# ExternalConnection.net
KiCad netlist of a schematic drawn in Altium Designer
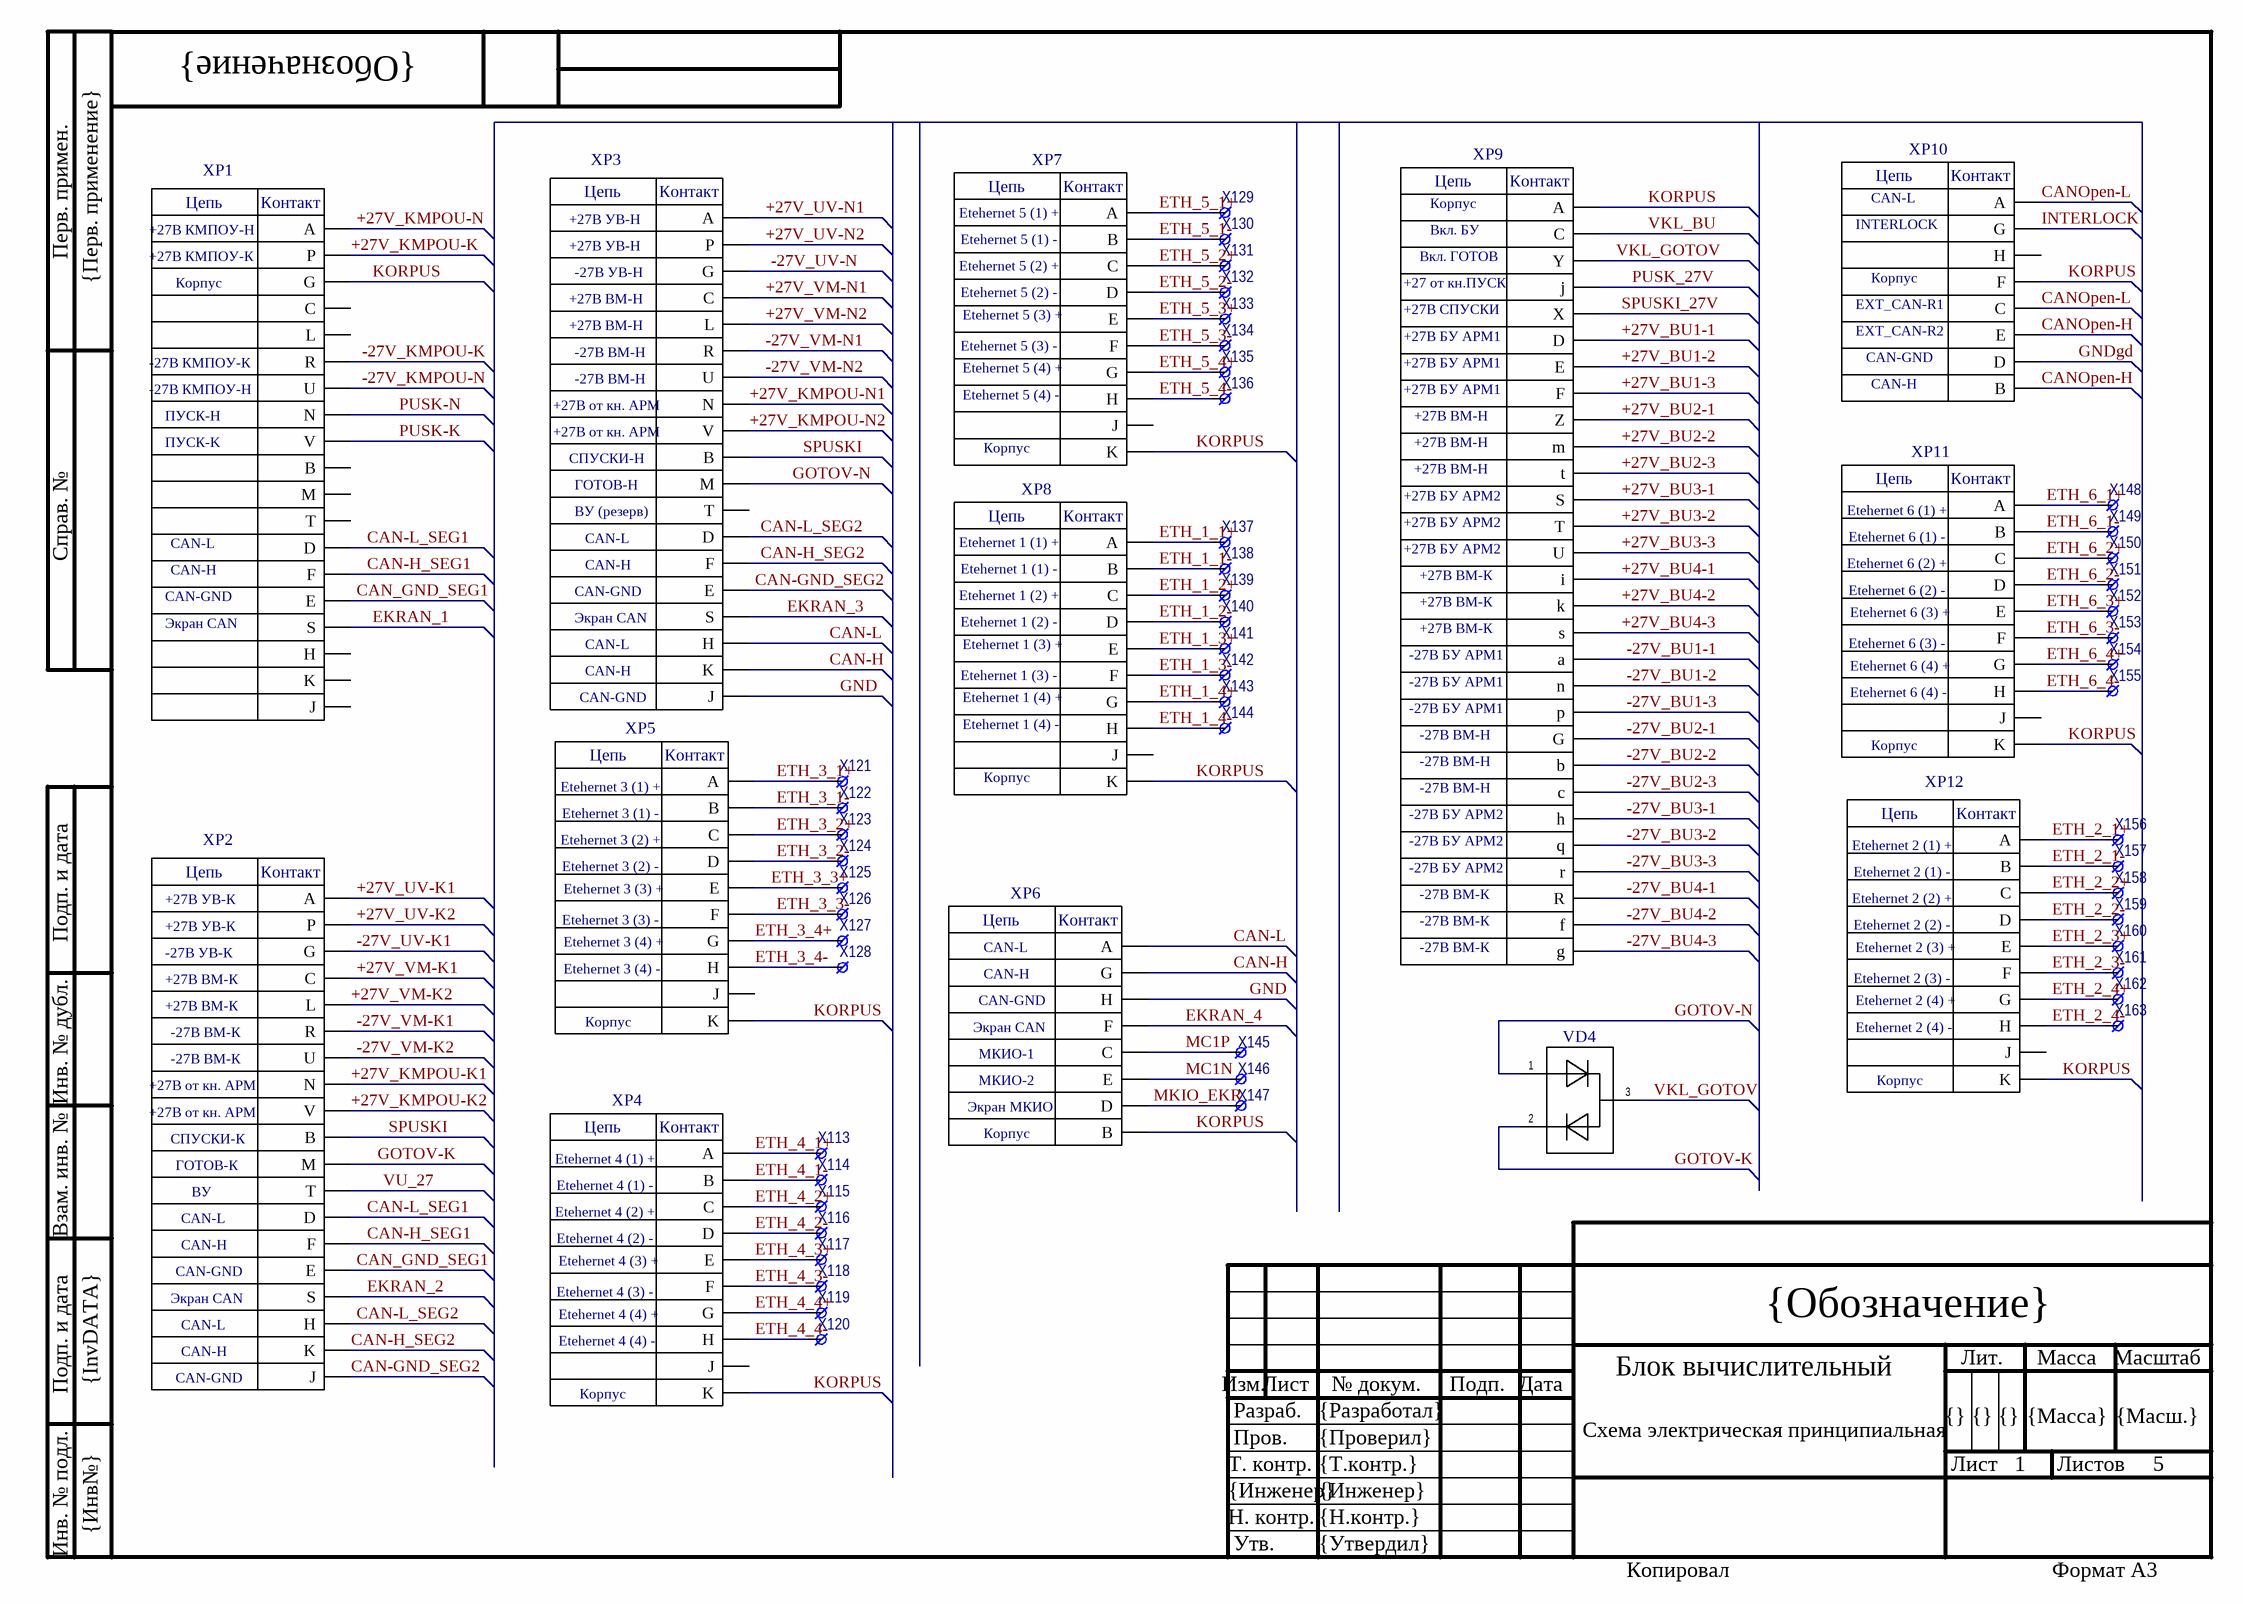
[diagram p0: ExternalConnection.SchDoc]

(export (version "E")
  (design (tool "Eeschema 10.0.6"))
  (components
    (comp (ref "VD4")
      (value "2Д707АС9")
      (footprint "KT-46")
      (description "2Д707АС9 диод импульсный")
      (libsource (lib "Блок вычислительный") (part "2Д707АС9"))
    )
    (comp (ref "X113")
      (value "CONT")
      (footprint "ПЛАН_ПЛОЩ")
      (description "CONT1_SMD")
      (fields (field (name "PARTNUMBER") "контактное поле"))
      (libsource (lib "Блок вычислительный") (part "CONT"))
    )
    (comp (ref "X114")
      (value "CONT")
      (footprint "ПЛАН_ПЛОЩ")
      (description "CONT1_SMD")
      (fields (field (name "PARTNUMBER") "контактное поле"))
      (libsource (lib "Блок вычислительный") (part "CONT"))
    )
    (comp (ref "X115")
      (value "CONT")
      (footprint "ПЛАН_ПЛОЩ")
      (description "CONT1_SMD")
      (fields (field (name "PARTNUMBER") "контактное поле"))
      (libsource (lib "Блок вычислительный") (part "CONT"))
    )
    (comp (ref "X116")
      (value "CONT")
      (footprint "ПЛАН_ПЛОЩ")
      (description "CONT1_SMD")
      (fields (field (name "PARTNUMBER") "контактное поле"))
      (libsource (lib "Блок вычислительный") (part "CONT"))
    )
    (comp (ref "X117")
      (value "CONT")
      (footprint "ПЛАН_ПЛОЩ")
      (description "CONT1_SMD")
      (fields (field (name "PARTNUMBER") "контактное поле"))
      (libsource (lib "Блок вычислительный") (part "CONT"))
    )
    (comp (ref "X118")
      (value "CONT")
      (footprint "ПЛАН_ПЛОЩ")
      (description "CONT1_SMD")
      (fields (field (name "PARTNUMBER") "контактное поле"))
      (libsource (lib "Блок вычислительный") (part "CONT"))
    )
    (comp (ref "X119")
      (value "CONT")
      (footprint "ПЛАН_ПЛОЩ")
      (description "CONT1_SMD")
      (fields (field (name "PARTNUMBER") "контактное поле"))
      (libsource (lib "Блок вычислительный") (part "CONT"))
    )
    (comp (ref "X120")
      (value "CONT")
      (footprint "ПЛАН_ПЛОЩ")
      (description "CONT1_SMD")
      (fields (field (name "PARTNUMBER") "контактное поле"))
      (libsource (lib "Блок вычислительный") (part "CONT"))
    )
    (comp (ref "X121")
      (value "CONT")
      (footprint "ПЛАН_ПЛОЩ")
      (description "CONT1_SMD")
      (fields (field (name "PARTNUMBER") "контактное поле"))
      (libsource (lib "Блок вычислительный") (part "CONT"))
    )
    (comp (ref "X122")
      (value "CONT")
      (footprint "ПЛАН_ПЛОЩ")
      (description "CONT1_SMD")
      (fields (field (name "PARTNUMBER") "контактное поле"))
      (libsource (lib "Блок вычислительный") (part "CONT"))
    )
    (comp (ref "X123")
      (value "CONT")
      (footprint "ПЛАН_ПЛОЩ")
      (description "CONT1_SMD")
      (fields (field (name "PARTNUMBER") "контактное поле"))
      (libsource (lib "Блок вычислительный") (part "CONT"))
    )
    (comp (ref "X124")
      (value "CONT")
      (footprint "ПЛАН_ПЛОЩ")
      (description "CONT1_SMD")
      (fields (field (name "PARTNUMBER") "контактное поле"))
      (libsource (lib "Блок вычислительный") (part "CONT"))
    )
    (comp (ref "X125")
      (value "CONT")
      (footprint "ПЛАН_ПЛОЩ")
      (description "CONT1_SMD")
      (fields (field (name "PARTNUMBER") "контактное поле"))
      (libsource (lib "Блок вычислительный") (part "CONT"))
    )
    (comp (ref "X126")
      (value "CONT")
      (footprint "ПЛАН_ПЛОЩ")
      (description "CONT1_SMD")
      (fields (field (name "PARTNUMBER") "контактное поле"))
      (libsource (lib "Блок вычислительный") (part "CONT"))
    )
    (comp (ref "X127")
      (value "CONT")
      (footprint "ПЛАН_ПЛОЩ")
      (description "CONT1_SMD")
      (fields (field (name "PARTNUMBER") "контактное поле"))
      (libsource (lib "Блок вычислительный") (part "CONT"))
    )
    (comp (ref "X128")
      (value "CONT")
      (footprint "ПЛАН_ПЛОЩ")
      (description "CONT1_SMD")
      (fields (field (name "PARTNUMBER") "контактное поле"))
      (libsource (lib "Блок вычислительный") (part "CONT"))
    )
    (comp (ref "X129")
      (value "CONT")
      (footprint "ПЛАН_ПЛОЩ")
      (description "CONT1_SMD")
      (fields (field (name "PARTNUMBER") "контактное поле"))
      (libsource (lib "Блок вычислительный") (part "CONT"))
    )
    (comp (ref "X130")
      (value "CONT")
      (footprint "ПЛАН_ПЛОЩ")
      (description "CONT1_SMD")
      (fields (field (name "PARTNUMBER") "контактное поле"))
      (libsource (lib "Блок вычислительный") (part "CONT"))
    )
    (comp (ref "X131")
      (value "CONT")
      (footprint "ПЛАН_ПЛОЩ")
      (description "CONT1_SMD")
      (fields (field (name "PARTNUMBER") "контактное поле"))
      (libsource (lib "Блок вычислительный") (part "CONT"))
    )
    (comp (ref "X132")
      (value "CONT")
      (footprint "ПЛАН_ПЛОЩ")
      (description "CONT1_SMD")
      (fields (field (name "PARTNUMBER") "контактное поле"))
      (libsource (lib "Блок вычислительный") (part "CONT"))
    )
    (comp (ref "X133")
      (value "CONT")
      (footprint "ПЛАН_ПЛОЩ")
      (description "CONT1_SMD")
      (fields (field (name "PARTNUMBER") "контактное поле"))
      (libsource (lib "Блок вычислительный") (part "CONT"))
    )
    (comp (ref "X134")
      (value "CONT")
      (footprint "ПЛАН_ПЛОЩ")
      (description "CONT1_SMD")
      (fields (field (name "PARTNUMBER") "контактное поле"))
      (libsource (lib "Блок вычислительный") (part "CONT"))
    )
    (comp (ref "X135")
      (value "CONT")
      (footprint "ПЛАН_ПЛОЩ")
      (description "CONT1_SMD")
      (fields (field (name "PARTNUMBER") "контактное поле"))
      (libsource (lib "Блок вычислительный") (part "CONT"))
    )
    (comp (ref "X136")
      (value "CONT")
      (footprint "ПЛАН_ПЛОЩ")
      (description "CONT1_SMD")
      (fields (field (name "PARTNUMBER") "контактное поле"))
      (libsource (lib "Блок вычислительный") (part "CONT"))
    )
    (comp (ref "X137")
      (value "CONT")
      (footprint "ПЛАН_ПЛОЩ")
      (description "CONT1_SMD")
      (fields (field (name "PARTNUMBER") "контактное поле"))
      (libsource (lib "Блок вычислительный") (part "CONT"))
    )
    (comp (ref "X138")
      (value "CONT")
      (footprint "ПЛАН_ПЛОЩ")
      (description "CONT1_SMD")
      (fields (field (name "PARTNUMBER") "контактное поле"))
      (libsource (lib "Блок вычислительный") (part "CONT"))
    )
    (comp (ref "X139")
      (value "CONT")
      (footprint "ПЛАН_ПЛОЩ")
      (description "CONT1_SMD")
      (fields (field (name "PARTNUMBER") "контактное поле"))
      (libsource (lib "Блок вычислительный") (part "CONT"))
    )
    (comp (ref "X140")
      (value "CONT")
      (footprint "ПЛАН_ПЛОЩ")
      (description "CONT1_SMD")
      (fields (field (name "PARTNUMBER") "контактное поле"))
      (libsource (lib "Блок вычислительный") (part "CONT"))
    )
    (comp (ref "X141")
      (value "CONT")
      (footprint "ПЛАН_ПЛОЩ")
      (description "CONT1_SMD")
      (fields (field (name "PARTNUMBER") "контактное поле"))
      (libsource (lib "Блок вычислительный") (part "CONT"))
    )
    (comp (ref "X142")
      (value "CONT")
      (footprint "ПЛАН_ПЛОЩ")
      (description "CONT1_SMD")
      (fields (field (name "PARTNUMBER") "контактное поле"))
      (libsource (lib "Блок вычислительный") (part "CONT"))
    )
    (comp (ref "X143")
      (value "CONT")
      (footprint "ПЛАН_ПЛОЩ")
      (description "CONT1_SMD")
      (fields (field (name "PARTNUMBER") "контактное поле"))
      (libsource (lib "Блок вычислительный") (part "CONT"))
    )
    (comp (ref "X144")
      (value "CONT")
      (footprint "ПЛАН_ПЛОЩ")
      (description "CONT1_SMD")
      (fields (field (name "PARTNUMBER") "контактное поле"))
      (libsource (lib "Блок вычислительный") (part "CONT"))
    )
    (comp (ref "X145")
      (value "CONT")
      (footprint "ПЛАН_ПЛОЩ")
      (description "CONT1_SMD")
      (fields (field (name "PARTNUMBER") "контактное поле"))
      (libsource (lib "Блок вычислительный") (part "CONT"))
    )
    (comp (ref "X146")
      (value "CONT")
      (footprint "ПЛАН_ПЛОЩ")
      (description "CONT1_SMD")
      (fields (field (name "PARTNUMBER") "контактное поле"))
      (libsource (lib "Блок вычислительный") (part "CONT"))
    )
    (comp (ref "X147")
      (value "CONT")
      (footprint "ПЛАН_ПЛОЩ")
      (description "CONT1_SMD")
      (fields (field (name "PARTNUMBER") "контактное поле"))
      (libsource (lib "Блок вычислительный") (part "CONT"))
    )
    (comp (ref "X148")
      (value "CONT")
      (footprint "ПЛАН_ПЛОЩ")
      (description "CONT1_SMD")
      (fields (field (name "PARTNUMBER") "контактное поле"))
      (libsource (lib "Блок вычислительный") (part "CONT"))
    )
    (comp (ref "X149")
      (value "CONT")
      (footprint "ПЛАН_ПЛОЩ")
      (description "CONT1_SMD")
      (fields (field (name "PARTNUMBER") "контактное поле"))
      (libsource (lib "Блок вычислительный") (part "CONT"))
    )
    (comp (ref "X150")
      (value "CONT")
      (footprint "ПЛАН_ПЛОЩ")
      (description "CONT1_SMD")
      (fields (field (name "PARTNUMBER") "контактное поле"))
      (libsource (lib "Блок вычислительный") (part "CONT"))
    )
    (comp (ref "X151")
      (value "CONT")
      (footprint "ПЛАН_ПЛОЩ")
      (description "CONT1_SMD")
      (fields (field (name "PARTNUMBER") "контактное поле"))
      (libsource (lib "Блок вычислительный") (part "CONT"))
    )
    (comp (ref "X152")
      (value "CONT")
      (footprint "ПЛАН_ПЛОЩ")
      (description "CONT1_SMD")
      (fields (field (name "PARTNUMBER") "контактное поле"))
      (libsource (lib "Блок вычислительный") (part "CONT"))
    )
    (comp (ref "X153")
      (value "CONT")
      (footprint "ПЛАН_ПЛОЩ")
      (description "CONT1_SMD")
      (fields (field (name "PARTNUMBER") "контактное поле"))
      (libsource (lib "Блок вычислительный") (part "CONT"))
    )
    (comp (ref "X154")
      (value "CONT")
      (footprint "ПЛАН_ПЛОЩ")
      (description "CONT1_SMD")
      (fields (field (name "PARTNUMBER") "контактное поле"))
      (libsource (lib "Блок вычислительный") (part "CONT"))
    )
    (comp (ref "X155")
      (value "CONT")
      (footprint "ПЛАН_ПЛОЩ")
      (description "CONT1_SMD")
      (fields (field (name "PARTNUMBER") "контактное поле"))
      (libsource (lib "Блок вычислительный") (part "CONT"))
    )
    (comp (ref "X156")
      (value "CONT")
      (footprint "ПЛАН_ПЛОЩ")
      (description "CONT1_SMD")
      (fields (field (name "PARTNUMBER") "контактное поле"))
      (libsource (lib "Блок вычислительный") (part "CONT"))
    )
    (comp (ref "X157")
      (value "CONT")
      (footprint "ПЛАН_ПЛОЩ")
      (description "CONT1_SMD")
      (fields (field (name "PARTNUMBER") "контактное поле"))
      (libsource (lib "Блок вычислительный") (part "CONT"))
    )
    (comp (ref "X158")
      (value "CONT")
      (footprint "ПЛАН_ПЛОЩ")
      (description "CONT1_SMD")
      (fields (field (name "PARTNUMBER") "контактное поле"))
      (libsource (lib "Блок вычислительный") (part "CONT"))
    )
    (comp (ref "X159")
      (value "CONT")
      (footprint "ПЛАН_ПЛОЩ")
      (description "CONT1_SMD")
      (fields (field (name "PARTNUMBER") "контактное поле"))
      (libsource (lib "Блок вычислительный") (part "CONT"))
    )
    (comp (ref "X160")
      (value "CONT")
      (footprint "ПЛАН_ПЛОЩ")
      (description "CONT1_SMD")
      (fields (field (name "PARTNUMBER") "контактное поле"))
      (libsource (lib "Блок вычислительный") (part "CONT"))
    )
    (comp (ref "X161")
      (value "CONT")
      (footprint "ПЛАН_ПЛОЩ")
      (description "CONT1_SMD")
      (fields (field (name "PARTNUMBER") "контактное поле"))
      (libsource (lib "Блок вычислительный") (part "CONT"))
    )
    (comp (ref "X162")
      (value "CONT")
      (footprint "ПЛАН_ПЛОЩ")
      (description "CONT1_SMD")
      (fields (field (name "PARTNUMBER") "контактное поле"))
      (libsource (lib "Блок вычислительный") (part "CONT"))
    )
    (comp (ref "X163")
      (value "CONT")
      (footprint "ПЛАН_ПЛОЩ")
      (description "CONT1_SMD")
      (fields (field (name "PARTNUMBER") "контактное поле"))
      (libsource (lib "Блок вычислительный") (part "CONT"))
    )
    (comp (ref "XP1")
      (value "СНЦ144-19")
      (footprint "блок вычислительный_v1:XP_СНЦ144-19/15-вилка")
      (description "ВИЛКА СНЦ144-19 СОСТАВНАЯ")
      (fields (field (name "PARTNUMBER") "СНЦ144-19/15ВП21-NWПС"))
      (libsource (lib "Блок вычислительный") (part "СНЦ144-19"))
    )
    (comp (ref "XP2")
      (value "СНЦ144-19")
      (footprint "блок вычислительный_v1:XP_СНЦ144-19/15-вилка")
      (description "ВИЛКА СНЦ144-19 СОСТАВНАЯ")
      (fields (field (name "PARTNUMBER") "СНЦ144-19/15ВП21-NWПС"))
      (libsource (lib "Блок вычислительный") (part "СНЦ144-19"))
    )
    (comp (ref "XP3")
      (value "СНЦ144-19")
      (footprint "блок вычислительный_v1:XP_СНЦ144-19/15-вилка")
      (description "ВИЛКА СНЦ144-19 СОСТАВНАЯ")
      (fields (field (name "PARTNUMBER") "СНЦ144-19/15ВП21-NWПС"))
      (libsource (lib "Блок вычислительный") (part "СНЦ144-19"))
    )
    (comp (ref "XP4")
      (value "СНЦ144-10")
      (footprint "блок вычислительный_v1:XP_СНЦ144-10_13-вилка")
      (description "ВИЛКА СНЦ144-10 СОСТАВНАЯ")
      (fields (field (name "PARTNUMBER") "СНЦ144-10/13ВП21-NWПС"))
      (libsource (lib "Блок вычислительный") (part "СНЦ144-10"))
    )
    (comp (ref "XP5")
      (value "СНЦ144-10")
      (footprint "блок вычислительный_v1:XP_СНЦ144-10_13-вилка")
      (description "ВИЛКА СНЦ144-10 СОСТАВНАЯ")
      (fields (field (name "PARTNUMBER") "СНЦ144-10/13ВП21-NWПС"))
      (libsource (lib "Блок вычислительный") (part "СНЦ144-10"))
    )
    (comp (ref "XP6")
      (value "СНЦ144-8")
      (footprint "блок вычислительный_v1:XP_СНЦ144-8_13-Вилка")
      (description "ВИЛКА СНЦ144-8 СОСТАВНАЯ")
      (fields (field (name "PARTNUMBER") "СНЦ144-8/13ВП21-NWПС"))
      (libsource (lib "Блок вычислительный") (part "СНЦ144-8"))
    )
    (comp (ref "XP7")
      (value "СНЦ144-10")
      (footprint "блок вычислительный_v1:XP_СНЦ144-10_13-вилка")
      (description "ВИЛКА СНЦ144-10 СОСТАВНАЯ")
      (fields (field (name "PARTNUMBER") "СНЦ144-10/13ВП21-NWПС"))
      (libsource (lib "Блок вычислительный") (part "СНЦ144-10"))
    )
    (comp (ref "XP8")
      (value "СНЦ144-10")
      (footprint "блок вычислительный_v1:XP_СНЦ144-10_13-вилка")
      (description "ВИЛКА СНЦ144-10 СОСТАВНАЯ")
      (fields (field (name "PARTNUMBER") "СНЦ144-10/13ВП21-NWПС"))
      (libsource (lib "Блок вычислительный") (part "СНЦ144-10"))
    )
    (comp (ref "XP9")
      (value "СНЦ144-41")
      (footprint "блок вычислительный_v1:XP_СНЦ144-41_21-вилка")
      (description "ВИЛКА СНЦ144-41 СОСТАВНАЯ")
      (fields (field (name "PARTNUMBER") "СНЦ144-41/21ВП21-NWПС"))
      (libsource (lib "Блок вычислительный") (part "СНЦ144-41"))
    )
    (comp (ref "XP10")
      (value "СНЦ144-8")
      (footprint "блок вычислительный_v1:XP_СНЦ144-8_13-Вилка")
      (description "ВИЛКА СНЦ144-8 СОСТАВНАЯ")
      (fields (field (name "PARTNUMBER") "СНЦ144-8/13ВП21-NWПС"))
      (libsource (lib "Блок вычислительный") (part "СНЦ144-8"))
    )
    (comp (ref "XP11")
      (value "СНЦ144-10")
      (footprint "блок вычислительный_v1:XP_СНЦ144-10_13-вилка")
      (description "ВИЛКА СНЦ144-10 СОСТАВНАЯ")
      (fields (field (name "PARTNUMBER") "СНЦ144-10/13ВП21-NWПС"))
      (libsource (lib "Блок вычислительный") (part "СНЦ144-10"))
    )
    (comp (ref "XP12")
      (value "СНЦ144-10")
      (footprint "блок вычислительный_v1:XP_СНЦ144-10_13-вилка")
      (description "ВИЛКА СНЦ144-10 СОСТАВНАЯ")
      (fields (field (name "PARTNUMBER") "СНЦ144-10/13ВП21-NWПС"))
      (libsource (lib "Блок вычислительный") (part "СНЦ144-10"))
    )
  )
  (nets
    (net (code "1") (name "/+27V_BU1-1") (class "Default")
      (node (ref "XP9") (pin "D") (pinfunction "D_D") (pintype "passive"))
    )
    (net (code "2") (name "/+27V_BU1-2") (class "Default")
      (node (ref "XP9") (pin "E") (pinfunction "E_E") (pintype "passive"))
    )
    (net (code "3") (name "/+27V_BU1-3") (class "Default")
      (node (ref "XP9") (pin "F") (pinfunction "F_F") (pintype "passive"))
    )
    (net (code "4") (name "/+27V_BU2-1") (class "Default")
      (node (ref "XP9") (pin "Z") (pinfunction "Z_Z") (pintype "passive"))
    )
    (net (code "5") (name "/+27V_BU2-2") (class "Default")
      (node (ref "XP9") (pin "mm") (pinfunction "m_mm") (pintype "passive"))
    )
    (net (code "6") (name "/+27V_BU2-3") (class "Default")
      (node (ref "XP9") (pin "tt") (pinfunction "t_tt") (pintype "passive"))
    )
    (net (code "7") (name "/+27V_BU3-1") (class "Default")
      (node (ref "XP9") (pin "S") (pinfunction "S_S") (pintype "passive"))
    )
    (net (code "8") (name "/+27V_BU3-2") (class "Default")
      (node (ref "XP9") (pin "T") (pinfunction "T_T") (pintype "passive"))
    )
    (net (code "9") (name "/+27V_BU3-3") (class "Default")
      (node (ref "XP9") (pin "U") (pinfunction "U_U") (pintype "passive"))
    )
    (net (code "10") (name "/+27V_BU4-1") (class "Default")
      (node (ref "XP9") (pin "ii") (pinfunction "i_ii") (pintype "passive"))
    )
    (net (code "11") (name "/+27V_BU4-2") (class "Default")
      (node (ref "XP9") (pin "kk") (pinfunction "k_kk") (pintype "passive"))
    )
    (net (code "12") (name "/+27V_BU4-3") (class "Default")
      (node (ref "XP9") (pin "ss") (pinfunction "s_ss") (pintype "passive"))
    )
    (net (code "13") (name "/+27V_KMPOU-K") (class "Default")
      (node (ref "XP1") (pin "P") (pinfunction "P_P") (pintype "passive"))
    )
    (net (code "14") (name "/+27V_KMPOU-K1") (class "Default")
      (node (ref "XP2") (pin "N") (pinfunction "N_N") (pintype "passive"))
    )
    (net (code "15") (name "/+27V_KMPOU-K2") (class "Default")
      (node (ref "XP2") (pin "V") (pinfunction "V_V") (pintype "passive"))
    )
    (net (code "16") (name "/+27V_KMPOU-N") (class "Default")
      (node (ref "XP1") (pin "A") (pinfunction "A_A") (pintype "passive"))
    )
    (net (code "17") (name "/+27V_KMPOU-N1") (class "Default")
      (node (ref "XP3") (pin "N") (pinfunction "N_N") (pintype "passive"))
    )
    (net (code "18") (name "/+27V_KMPOU-N2") (class "Default")
      (node (ref "XP3") (pin "V") (pinfunction "V_V") (pintype "passive"))
    )
    (net (code "19") (name "/+27V_UV-K1") (class "Default")
      (node (ref "XP2") (pin "A") (pinfunction "A_A") (pintype "passive"))
    )
    (net (code "20") (name "/+27V_UV-K2") (class "Default")
      (node (ref "XP2") (pin "P") (pinfunction "P_P") (pintype "passive"))
    )
    (net (code "21") (name "/+27V_UV-N1") (class "Default")
      (node (ref "XP3") (pin "A") (pinfunction "A_A") (pintype "passive"))
    )
    (net (code "22") (name "/+27V_UV-N2") (class "Default")
      (node (ref "XP3") (pin "P") (pinfunction "P_P") (pintype "passive"))
    )
    (net (code "23") (name "/+27V_VM-K1") (class "Default")
      (node (ref "XP2") (pin "C") (pinfunction "C_C") (pintype "passive"))
    )
    (net (code "24") (name "/+27V_VM-K2") (class "Default")
      (node (ref "XP2") (pin "L") (pinfunction "L_L") (pintype "passive"))
    )
    (net (code "25") (name "/+27V_VM-N1") (class "Default")
      (node (ref "XP3") (pin "C") (pinfunction "C_C") (pintype "passive"))
    )
    (net (code "26") (name "/+27V_VM-N2") (class "Default")
      (node (ref "XP3") (pin "L") (pinfunction "L_L") (pintype "passive"))
    )
    (net (code "27") (name "/-27V_BU1-1") (class "Default")
      (node (ref "XP9") (pin "aa") (pinfunction "a_aa") (pintype "passive"))
    )
    (net (code "28") (name "/-27V_BU1-2") (class "Default")
      (node (ref "XP9") (pin "nn") (pinfunction "n_nn") (pintype "passive"))
    )
    (net (code "29") (name "/-27V_BU1-3") (class "Default")
      (node (ref "XP9") (pin "pp") (pinfunction "p_pp") (pintype "passive"))
    )
    (net (code "30") (name "/-27V_BU2-1") (class "Default")
      (node (ref "XP9") (pin "G") (pinfunction "G_G") (pintype "passive"))
    )
    (net (code "31") (name "/-27V_BU2-2") (class "Default")
      (node (ref "XP9") (pin "bb") (pinfunction "b_bb") (pintype "passive"))
    )
    (net (code "32") (name "/-27V_BU2-3") (class "Default")
      (node (ref "XP9") (pin "cc") (pinfunction "c_cc") (pintype "passive"))
    )
    (net (code "33") (name "/-27V_BU3-1") (class "Default")
      (node (ref "XP9") (pin "hh") (pinfunction "h_hh") (pintype "passive"))
    )
    (net (code "34") (name "/-27V_BU3-2") (class "Default")
      (node (ref "XP9") (pin "qq") (pinfunction "q_qq") (pintype "passive"))
    )
    (net (code "35") (name "/-27V_BU3-3") (class "Default")
      (node (ref "XP9") (pin "rr") (pinfunction "r_rr") (pintype "passive"))
    )
    (net (code "36") (name "/-27V_BU4-1") (class "Default")
      (node (ref "XP9") (pin "R") (pinfunction "R_R") (pintype "passive"))
    )
    (net (code "37") (name "/-27V_BU4-2") (class "Default")
      (node (ref "XP9") (pin "ff") (pinfunction "f_ff") (pintype "passive"))
    )
    (net (code "38") (name "/-27V_BU4-3") (class "Default")
      (node (ref "XP9") (pin "gg") (pinfunction "g_gg") (pintype "passive"))
    )
    (net (code "39") (name "/-27V_KMPOU-K") (class "Default")
      (node (ref "XP1") (pin "R") (pinfunction "R_R") (pintype "passive"))
    )
    (net (code "40") (name "/-27V_KMPOU-N") (class "Default")
      (node (ref "XP1") (pin "U") (pinfunction "U_U") (pintype "passive"))
    )
    (net (code "41") (name "/-27V_UV-K1") (class "Default")
      (node (ref "XP2") (pin "G") (pinfunction "G_G") (pintype "passive"))
    )
    (net (code "42") (name "/-27V_UV-N") (class "Default")
      (node (ref "XP3") (pin "G") (pinfunction "G_G") (pintype "passive"))
    )
    (net (code "43") (name "/-27V_VM-K1") (class "Default")
      (node (ref "XP2") (pin "R") (pinfunction "R_R") (pintype "passive"))
    )
    (net (code "44") (name "/-27V_VM-K2") (class "Default")
      (node (ref "XP2") (pin "U") (pinfunction "U_U") (pintype "passive"))
    )
    (net (code "45") (name "/-27V_VM-N1") (class "Default")
      (node (ref "XP3") (pin "R") (pinfunction "R_R") (pintype "passive"))
    )
    (net (code "46") (name "/-27V_VM-N2") (class "Default")
      (node (ref "XP3") (pin "U") (pinfunction "U_U") (pintype "passive"))
    )
    (net (code "47") (name "/CAN-GND_SEG2") (class "Default")
      (node (ref "XP2") (pin "J") (pinfunction "J_J") (pintype "passive"))
      (node (ref "XP3") (pin "E") (pinfunction "E_E") (pintype "passive"))
    )
    (net (code "48") (name "/CAN-H") (class "Default")
      (node (ref "XP3") (pin "K") (pinfunction "K_K") (pintype "passive"))
      (node (ref "XP6") (pin "G") (pinfunction "G_G") (pintype "passive"))
    )
    (net (code "49") (name "/CAN-H_SEG1") (class "Default")
      (node (ref "XP1") (pin "F") (pinfunction "F_F") (pintype "passive"))
      (node (ref "XP2") (pin "F") (pinfunction "F_F") (pintype "passive"))
    )
    (net (code "50") (name "/CAN-H_SEG2") (class "Default")
      (node (ref "XP2") (pin "K") (pinfunction "K_K") (pintype "passive"))
      (node (ref "XP3") (pin "F") (pinfunction "F_F") (pintype "passive"))
    )
    (net (code "51") (name "/CAN-L") (class "Default")
      (node (ref "XP3") (pin "H") (pinfunction "H_H") (pintype "passive"))
      (node (ref "XP6") (pin "A") (pinfunction "A_A") (pintype "passive"))
    )
    (net (code "52") (name "/CAN-L_SEG1") (class "Default")
      (node (ref "XP1") (pin "D") (pinfunction "D_D") (pintype "passive"))
      (node (ref "XP2") (pin "D") (pinfunction "D_D") (pintype "passive"))
    )
    (net (code "53") (name "/CAN-L_SEG2") (class "Default")
      (node (ref "XP2") (pin "H") (pinfunction "H_H") (pintype "passive"))
      (node (ref "XP3") (pin "D") (pinfunction "D_D") (pintype "passive"))
    )
    (net (code "54") (name "/CANOpen-H") (class "Default")
      (node (ref "XP10") (pin "B") (pinfunction "B_B") (pintype "passive"))
      (node (ref "XP10") (pin "E") (pinfunction "E_E") (pintype "passive"))
    )
    (net (code "55") (name "/CANOpen-L") (class "Default")
      (node (ref "XP10") (pin "A") (pinfunction "A_A") (pintype "passive"))
      (node (ref "XP10") (pin "C") (pinfunction "C_C") (pintype "passive"))
    )
    (net (code "56") (name "/CAN_GND_SEG1") (class "Default")
      (node (ref "XP1") (pin "E") (pinfunction "E_E") (pintype "passive"))
      (node (ref "XP2") (pin "E") (pinfunction "E_E") (pintype "passive"))
    )
    (net (code "57") (name "/EKRAN_1") (class "Default")
      (node (ref "XP1") (pin "S") (pinfunction "S_S") (pintype "passive"))
    )
    (net (code "58") (name "/EKRAN_2") (class "Default")
      (node (ref "XP2") (pin "S") (pinfunction "S_S") (pintype "passive"))
    )
    (net (code "59") (name "/EKRAN_3") (class "Default")
      (node (ref "XP3") (pin "S") (pinfunction "S_S") (pintype "passive"))
    )
    (net (code "60") (name "/EKRAN_4") (class "Default")
      (node (ref "XP6") (pin "F") (pinfunction "F_F") (pintype "passive"))
    )
    (net (code "61") (name "/ETH_1_1+") (class "Default")
      (node (ref "X137") (pin "1") (pinfunction "1_1") (pintype "passive"))
      (node (ref "XP8") (pin "A") (pinfunction "A_A") (pintype "passive"))
    )
    (net (code "62") (name "/ETH_1_1-") (class "Default")
      (node (ref "X138") (pin "1") (pinfunction "1_1") (pintype "passive"))
      (node (ref "XP8") (pin "B") (pinfunction "B_B") (pintype "passive"))
    )
    (net (code "63") (name "/ETH_1_2+") (class "Default")
      (node (ref "X139") (pin "1") (pinfunction "1_1") (pintype "passive"))
      (node (ref "XP8") (pin "C") (pinfunction "C_C") (pintype "passive"))
    )
    (net (code "64") (name "/ETH_1_2-") (class "Default")
      (node (ref "X140") (pin "1") (pinfunction "1_1") (pintype "passive"))
      (node (ref "XP8") (pin "D") (pinfunction "D_D") (pintype "passive"))
    )
    (net (code "65") (name "/ETH_1_3+") (class "Default")
      (node (ref "X141") (pin "1") (pinfunction "1_1") (pintype "passive"))
      (node (ref "XP8") (pin "E") (pinfunction "E_E") (pintype "passive"))
    )
    (net (code "66") (name "/ETH_1_3-") (class "Default")
      (node (ref "X142") (pin "1") (pinfunction "1_1") (pintype "passive"))
      (node (ref "XP8") (pin "F") (pinfunction "F_F") (pintype "passive"))
    )
    (net (code "67") (name "/ETH_1_4+") (class "Default")
      (node (ref "X143") (pin "1") (pinfunction "1_1") (pintype "passive"))
      (node (ref "XP8") (pin "G") (pinfunction "G_G") (pintype "passive"))
    )
    (net (code "68") (name "/ETH_1_4-") (class "Default")
      (node (ref "X144") (pin "1") (pinfunction "1_1") (pintype "passive"))
      (node (ref "XP8") (pin "H") (pinfunction "H_H") (pintype "passive"))
    )
    (net (code "69") (name "/ETH_2_1+") (class "Default")
      (node (ref "X156") (pin "1") (pinfunction "1_1") (pintype "passive"))
      (node (ref "XP12") (pin "A") (pinfunction "A_A") (pintype "passive"))
    )
    (net (code "70") (name "/ETH_2_1-") (class "Default")
      (node (ref "X157") (pin "1") (pinfunction "1_1") (pintype "passive"))
      (node (ref "XP12") (pin "B") (pinfunction "B_B") (pintype "passive"))
    )
    (net (code "71") (name "/ETH_2_2+") (class "Default")
      (node (ref "X158") (pin "1") (pinfunction "1_1") (pintype "passive"))
      (node (ref "XP12") (pin "C") (pinfunction "C_C") (pintype "passive"))
    )
    (net (code "72") (name "/ETH_2_2-") (class "Default")
      (node (ref "X159") (pin "1") (pinfunction "1_1") (pintype "passive"))
      (node (ref "XP12") (pin "D") (pinfunction "D_D") (pintype "passive"))
    )
    (net (code "73") (name "/ETH_2_3+") (class "Default")
      (node (ref "X160") (pin "1") (pinfunction "1_1") (pintype "passive"))
      (node (ref "XP12") (pin "E") (pinfunction "E_E") (pintype "passive"))
    )
    (net (code "74") (name "/ETH_2_3-") (class "Default")
      (node (ref "X161") (pin "1") (pinfunction "1_1") (pintype "passive"))
      (node (ref "XP12") (pin "F") (pinfunction "F_F") (pintype "passive"))
    )
    (net (code "75") (name "/ETH_2_4+") (class "Default")
      (node (ref "X162") (pin "1") (pinfunction "1_1") (pintype "passive"))
      (node (ref "XP12") (pin "G") (pinfunction "G_G") (pintype "passive"))
    )
    (net (code "76") (name "/ETH_2_4-") (class "Default")
      (node (ref "X163") (pin "1") (pinfunction "1_1") (pintype "passive"))
      (node (ref "XP12") (pin "H") (pinfunction "H_H") (pintype "passive"))
    )
    (net (code "77") (name "/ETH_3_1+") (class "Default")
      (node (ref "X121") (pin "1") (pinfunction "1_1") (pintype "passive"))
      (node (ref "XP5") (pin "A") (pinfunction "A_A") (pintype "passive"))
    )
    (net (code "78") (name "/ETH_3_1-") (class "Default")
      (node (ref "X122") (pin "1") (pinfunction "1_1") (pintype "passive"))
      (node (ref "XP5") (pin "B") (pinfunction "B_B") (pintype "passive"))
    )
    (net (code "79") (name "/ETH_3_2+") (class "Default")
      (node (ref "X123") (pin "1") (pinfunction "1_1") (pintype "passive"))
      (node (ref "XP5") (pin "C") (pinfunction "C_C") (pintype "passive"))
    )
    (net (code "80") (name "/ETH_3_2-") (class "Default")
      (node (ref "X124") (pin "1") (pinfunction "1_1") (pintype "passive"))
      (node (ref "XP5") (pin "D") (pinfunction "D_D") (pintype "passive"))
    )
    (net (code "81") (name "/ETH_3_3+") (class "Default")
      (node (ref "X125") (pin "1") (pinfunction "1_1") (pintype "passive"))
      (node (ref "XP5") (pin "E") (pinfunction "E_E") (pintype "passive"))
    )
    (net (code "82") (name "/ETH_3_3-") (class "Default")
      (node (ref "X126") (pin "1") (pinfunction "1_1") (pintype "passive"))
      (node (ref "XP5") (pin "F") (pinfunction "F_F") (pintype "passive"))
    )
    (net (code "83") (name "/ETH_3_4+") (class "Default")
      (node (ref "X127") (pin "1") (pinfunction "1_1") (pintype "passive"))
      (node (ref "XP5") (pin "G") (pinfunction "G_G") (pintype "passive"))
    )
    (net (code "84") (name "/ETH_3_4-") (class "Default")
      (node (ref "X128") (pin "1") (pinfunction "1_1") (pintype "passive"))
      (node (ref "XP5") (pin "H") (pinfunction "H_H") (pintype "passive"))
    )
    (net (code "85") (name "/ETH_4_1+") (class "Default")
      (node (ref "X113") (pin "1") (pinfunction "1_1") (pintype "passive"))
      (node (ref "XP4") (pin "A") (pinfunction "A_A") (pintype "passive"))
    )
    (net (code "86") (name "/ETH_4_1-") (class "Default")
      (node (ref "X114") (pin "1") (pinfunction "1_1") (pintype "passive"))
      (node (ref "XP4") (pin "B") (pinfunction "B_B") (pintype "passive"))
    )
    (net (code "87") (name "/ETH_4_2+") (class "Default")
      (node (ref "X115") (pin "1") (pinfunction "1_1") (pintype "passive"))
      (node (ref "XP4") (pin "C") (pinfunction "C_C") (pintype "passive"))
    )
    (net (code "88") (name "/ETH_4_2-") (class "Default")
      (node (ref "X116") (pin "1") (pinfunction "1_1") (pintype "passive"))
      (node (ref "XP4") (pin "D") (pinfunction "D_D") (pintype "passive"))
    )
    (net (code "89") (name "/ETH_4_3+") (class "Default")
      (node (ref "X117") (pin "1") (pinfunction "1_1") (pintype "passive"))
      (node (ref "XP4") (pin "E") (pinfunction "E_E") (pintype "passive"))
    )
    (net (code "90") (name "/ETH_4_3-") (class "Default")
      (node (ref "X118") (pin "1") (pinfunction "1_1") (pintype "passive"))
      (node (ref "XP4") (pin "F") (pinfunction "F_F") (pintype "passive"))
    )
    (net (code "91") (name "/ETH_4_4+") (class "Default")
      (node (ref "X119") (pin "1") (pinfunction "1_1") (pintype "passive"))
      (node (ref "XP4") (pin "G") (pinfunction "G_G") (pintype "passive"))
    )
    (net (code "92") (name "/ETH_4_4-") (class "Default")
      (node (ref "X120") (pin "1") (pinfunction "1_1") (pintype "passive"))
      (node (ref "XP4") (pin "H") (pinfunction "H_H") (pintype "passive"))
    )
    (net (code "93") (name "/ETH_5_1+") (class "Default")
      (node (ref "X129") (pin "1") (pinfunction "1_1") (pintype "passive"))
      (node (ref "XP7") (pin "A") (pinfunction "A_A") (pintype "passive"))
    )
    (net (code "94") (name "/ETH_5_1-") (class "Default")
      (node (ref "X130") (pin "1") (pinfunction "1_1") (pintype "passive"))
      (node (ref "XP7") (pin "B") (pinfunction "B_B") (pintype "passive"))
    )
    (net (code "95") (name "/ETH_5_2+") (class "Default")
      (node (ref "X131") (pin "1") (pinfunction "1_1") (pintype "passive"))
      (node (ref "XP7") (pin "C") (pinfunction "C_C") (pintype "passive"))
    )
    (net (code "96") (name "/ETH_5_2-") (class "Default")
      (node (ref "X132") (pin "1") (pinfunction "1_1") (pintype "passive"))
      (node (ref "XP7") (pin "D") (pinfunction "D_D") (pintype "passive"))
    )
    (net (code "97") (name "/ETH_5_3+") (class "Default")
      (node (ref "X133") (pin "1") (pinfunction "1_1") (pintype "passive"))
      (node (ref "XP7") (pin "E") (pinfunction "E_E") (pintype "passive"))
    )
    (net (code "98") (name "/ETH_5_3-") (class "Default")
      (node (ref "X134") (pin "1") (pinfunction "1_1") (pintype "passive"))
      (node (ref "XP7") (pin "F") (pinfunction "F_F") (pintype "passive"))
    )
    (net (code "99") (name "/ETH_5_4+") (class "Default")
      (node (ref "X135") (pin "1") (pinfunction "1_1") (pintype "passive"))
      (node (ref "XP7") (pin "G") (pinfunction "G_G") (pintype "passive"))
    )
    (net (code "100") (name "/ETH_5_4-") (class "Default")
      (node (ref "X136") (pin "1") (pinfunction "1_1") (pintype "passive"))
      (node (ref "XP7") (pin "H") (pinfunction "H_H") (pintype "passive"))
    )
    (net (code "101") (name "/ETH_6_1+") (class "Default")
      (node (ref "X148") (pin "1") (pinfunction "1_1") (pintype "passive"))
      (node (ref "XP11") (pin "A") (pinfunction "A_A") (pintype "passive"))
    )
    (net (code "102") (name "/ETH_6_1-") (class "Default")
      (node (ref "X149") (pin "1") (pinfunction "1_1") (pintype "passive"))
      (node (ref "XP11") (pin "B") (pinfunction "B_B") (pintype "passive"))
    )
    (net (code "103") (name "/ETH_6_2+") (class "Default")
      (node (ref "X150") (pin "1") (pinfunction "1_1") (pintype "passive"))
      (node (ref "XP11") (pin "C") (pinfunction "C_C") (pintype "passive"))
    )
    (net (code "104") (name "/ETH_6_2-") (class "Default")
      (node (ref "X151") (pin "1") (pinfunction "1_1") (pintype "passive"))
      (node (ref "XP11") (pin "D") (pinfunction "D_D") (pintype "passive"))
    )
    (net (code "105") (name "/ETH_6_3+") (class "Default")
      (node (ref "X152") (pin "1") (pinfunction "1_1") (pintype "passive"))
      (node (ref "XP11") (pin "E") (pinfunction "E_E") (pintype "passive"))
    )
    (net (code "106") (name "/ETH_6_3-") (class "Default")
      (node (ref "X153") (pin "1") (pinfunction "1_1") (pintype "passive"))
      (node (ref "XP11") (pin "F") (pinfunction "F_F") (pintype "passive"))
    )
    (net (code "107") (name "/ETH_6_4+") (class "Default")
      (node (ref "X154") (pin "1") (pinfunction "1_1") (pintype "passive"))
      (node (ref "XP11") (pin "G") (pinfunction "G_G") (pintype "passive"))
    )
    (net (code "108") (name "/ETH_6_4-") (class "Default")
      (node (ref "X155") (pin "1") (pinfunction "1_1") (pintype "passive"))
      (node (ref "XP11") (pin "H") (pinfunction "H_H") (pintype "passive"))
    )
    (net (code "109") (name "/GND") (class "Default")
      (node (ref "XP3") (pin "J") (pinfunction "J_J") (pintype "passive"))
      (node (ref "XP6") (pin "H") (pinfunction "H_H") (pintype "passive"))
    )
    (net (code "110") (name "/GNDgd") (class "Default")
      (node (ref "XP10") (pin "D") (pinfunction "D_D") (pintype "passive"))
    )
    (net (code "111") (name "/GOTOV-K") (class "Default")
      (node (ref "VD4") (pin "2") (pinfunction "2_2") (pintype "passive"))
      (node (ref "XP2") (pin "M") (pinfunction "M_M") (pintype "passive"))
    )
    (net (code "112") (name "/GOTOV-N") (class "Default")
      (node (ref "VD4") (pin "1") (pinfunction "1_1") (pintype "passive"))
      (node (ref "XP3") (pin "M") (pinfunction "M_M") (pintype "passive"))
    )
    (net (code "113") (name "/INTERLOCK") (class "Default")
      (node (ref "XP10") (pin "G") (pinfunction "G_G") (pintype "passive"))
    )
    (net (code "114") (name "/KORPUS") (class "Default")
      (node (ref "XP1") (pin "G") (pinfunction "G_G") (pintype "passive"))
      (node (ref "XP10") (pin "F") (pinfunction "F_F") (pintype "passive"))
      (node (ref "XP11") (pin "K") (pinfunction "K_K") (pintype "passive"))
      (node (ref "XP12") (pin "K") (pinfunction "K_K") (pintype "passive"))
      (node (ref "XP4") (pin "K") (pinfunction "K_K") (pintype "passive"))
      (node (ref "XP5") (pin "K") (pinfunction "K_K") (pintype "passive"))
      (node (ref "XP6") (pin "B") (pinfunction "B_B") (pintype "passive"))
      (node (ref "XP7") (pin "K") (pinfunction "K_K") (pintype "passive"))
      (node (ref "XP8") (pin "K") (pinfunction "K_K") (pintype "passive"))
      (node (ref "XP9") (pin "A") (pinfunction "A_A") (pintype "passive"))
    )
    (net (code "115") (name "/MC1N") (class "Default")
      (node (ref "X146") (pin "1") (pinfunction "1_1") (pintype "passive"))
      (node (ref "XP6") (pin "E") (pinfunction "E_E") (pintype "passive"))
    )
    (net (code "116") (name "/MC1P") (class "Default")
      (node (ref "X145") (pin "1") (pinfunction "1_1") (pintype "passive"))
      (node (ref "XP6") (pin "C") (pinfunction "C_C") (pintype "passive"))
    )
    (net (code "117") (name "/MKIO_EKR") (class "Default")
      (node (ref "X147") (pin "1") (pinfunction "1_1") (pintype "passive"))
      (node (ref "XP6") (pin "D") (pinfunction "D_D") (pintype "passive"))
    )
    (net (code "118") (name "/PUSK-K") (class "Default")
      (node (ref "XP1") (pin "V") (pinfunction "V_V") (pintype "passive"))
    )
    (net (code "119") (name "/PUSK-N") (class "Default")
      (node (ref "XP1") (pin "N") (pinfunction "N_N") (pintype "passive"))
    )
    (net (code "120") (name "/PUSK_27V") (class "Default")
      (node (ref "XP9") (pin "jj") (pinfunction "j_jj") (pintype "passive"))
    )
    (net (code "121") (name "/SPUSKI") (class "Default")
      (node (ref "XP2") (pin "B") (pinfunction "B_B") (pintype "passive"))
      (node (ref "XP3") (pin "B") (pinfunction "B_B") (pintype "passive"))
    )
    (net (code "122") (name "/SPUSKI_27V") (class "Default")
      (node (ref "XP9") (pin "X") (pinfunction "X_X") (pintype "passive"))
    )
    (net (code "123") (name "/VKL_BU") (class "Default")
      (node (ref "XP9") (pin "C") (pinfunction "C_C") (pintype "passive"))
    )
    (net (code "124") (name "/VKL_GOTOV") (class "Default")
      (node (ref "VD4") (pin "3") (pinfunction "3_3") (pintype "passive"))
      (node (ref "XP9") (pin "Y") (pinfunction "Y_Y") (pintype "passive"))
    )
    (net (code "125") (name "/VU_27") (class "Default")
      (node (ref "XP2") (pin "T") (pinfunction "T_T") (pintype "passive"))
    )
    (net (code "126") (name "unconnected-(XP1-PadB)") (class "Default")
      (node (ref "XP1") (pin "B") (pinfunction "B_B") (pintype "passive"))
    )
    (net (code "127") (name "unconnected-(XP1-PadC)") (class "Default")
      (node (ref "XP1") (pin "C") (pinfunction "C_C") (pintype "passive"))
    )
    (net (code "128") (name "unconnected-(XP1-PadH)") (class "Default")
      (node (ref "XP1") (pin "H") (pinfunction "H_H") (pintype "passive"))
    )
    (net (code "129") (name "unconnected-(XP1-PadJ)") (class "Default")
      (node (ref "XP1") (pin "J") (pinfunction "J_J") (pintype "passive"))
    )
    (net (code "130") (name "unconnected-(XP1-PadK)") (class "Default")
      (node (ref "XP1") (pin "K") (pinfunction "K_K") (pintype "passive"))
    )
    (net (code "131") (name "unconnected-(XP1-PadL)") (class "Default")
      (node (ref "XP1") (pin "L") (pinfunction "L_L") (pintype "passive"))
    )
    (net (code "132") (name "unconnected-(XP1-PadM)") (class "Default")
      (node (ref "XP1") (pin "M") (pinfunction "M_M") (pintype "passive"))
    )
    (net (code "133") (name "unconnected-(XP1-PadT)") (class "Default")
      (node (ref "XP1") (pin "T") (pinfunction "T_T") (pintype "passive"))
    )
    (net (code "134") (name "unconnected-(XP3-PadT)") (class "Default")
      (node (ref "XP3") (pin "T") (pinfunction "T_T") (pintype "passive"))
    )
    (net (code "135") (name "unconnected-(XP4-PadJ)") (class "Default")
      (node (ref "XP4") (pin "J") (pinfunction "J_J") (pintype "passive"))
    )
    (net (code "136") (name "unconnected-(XP5-PadJ)") (class "Default")
      (node (ref "XP5") (pin "J") (pinfunction "J_J") (pintype "passive"))
    )
    (net (code "137") (name "unconnected-(XP7-PadJ)") (class "Default")
      (node (ref "XP7") (pin "J") (pinfunction "J_J") (pintype "passive"))
    )
    (net (code "138") (name "unconnected-(XP8-PadJ)") (class "Default")
      (node (ref "XP8") (pin "J") (pinfunction "J_J") (pintype "passive"))
    )
    (net (code "139") (name "unconnected-(XP10-PadH)") (class "Default")
      (node (ref "XP10") (pin "H") (pinfunction "H_H") (pintype "passive"))
    )
    (net (code "140") (name "unconnected-(XP11-PadJ)") (class "Default")
      (node (ref "XP11") (pin "J") (pinfunction "J_J") (pintype "passive"))
    )
    (net (code "141") (name "unconnected-(XP12-PadJ)") (class "Default")
      (node (ref "XP12") (pin "J") (pinfunction "J_J") (pintype "passive"))
    )
  )
)
